# charger.net
KiCad netlist of a schematic drawn in EAGLE
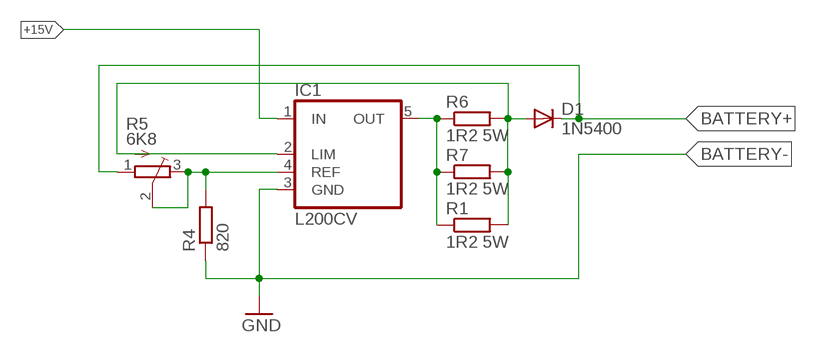
[diagram p0: schematic, sheet 1]

(export (version "E")
  (design (tool "Eeschema 10.0.6"))
  (components
    (comp (ref "D1")
      (value "1N5400")
      (footprint "eagle-import:DO201-15")
      (libsource (lib "eagle-import") (part "1N5400"))
    )
    (comp (ref "IC1")
      (value "L200CV")
      (footprint "eagle-import:L200S")
      (libsource (lib "eagle-import") (part "L200"))
    )
    (comp (ref "R1")
      (value "1R2 5W")
      (footprint "eagle-import:0204_7")
      (libsource (lib "eagle-import") (part "R-EU_0204/7"))
    )
    (comp (ref "R4")
      (value "820")
      (footprint "eagle-import:0204_7")
      (libsource (lib "eagle-import") (part "R-EU_0204/7"))
    )
    (comp (ref "R5")
      (value "6K8")
      (footprint "eagle-import:3223G")
      (libsource (lib "eagle-import") (part "TRIM_EU-3223G"))
    )
    (comp (ref "R6")
      (value "1R2 5W")
      (footprint "eagle-import:0204_7")
      (libsource (lib "eagle-import") (part "R-EU_0204/7"))
    )
    (comp (ref "R7")
      (value "1R2 5W")
      (footprint "eagle-import:0204_7")
      (libsource (lib "eagle-import") (part "R-EU_0204/7"))
    )
  )
  (nets
    (net (code "1") (name "+15V") (class "Default")
      (node (ref "IC1") (pin "1") (pinfunction "IN_1") (pintype "input"))
    )
    (net (code "2") (name "BATTERY+") (class "Default")
      (node (ref "D1") (pin "C") (pinfunction "C_C") (pintype "passive"))
      (node (ref "R5") (pin "1") (pinfunction "A_1") (pintype "passive"))
    )
    (net (code "3") (name "BATTERY-") (class "Default")
      (node (ref "IC1") (pin "3") (pinfunction "GND_3") (pintype "passive"))
      (node (ref "R4") (pin "1") (pinfunction "1_1") (pintype "passive"))
    )
    (net (code "4") (name "Net-(IC1-LIM)") (class "Default")
      (node (ref "D1") (pin "A") (pinfunction "A_A") (pintype "passive"))
      (node (ref "IC1") (pin "2") (pinfunction "LIM_2") (pintype "input"))
      (node (ref "R1") (pin "2") (pinfunction "2_2") (pintype "passive"))
      (node (ref "R6") (pin "2") (pinfunction "2_2") (pintype "passive"))
      (node (ref "R7") (pin "2") (pinfunction "2_2") (pintype "passive"))
    )
    (net (code "5") (name "Net-(IC1-OUT)") (class "Default")
      (node (ref "IC1") (pin "5") (pinfunction "OUT_5") (pintype "passive"))
      (node (ref "R1") (pin "1") (pinfunction "1_1") (pintype "passive"))
      (node (ref "R6") (pin "1") (pinfunction "1_1") (pintype "passive"))
      (node (ref "R7") (pin "1") (pinfunction "1_1") (pintype "passive"))
    )
    (net (code "6") (name "Net-(IC1-REF)") (class "Default")
      (node (ref "IC1") (pin "4") (pinfunction "REF_4") (pintype "input"))
      (node (ref "R4") (pin "2") (pinfunction "2_2") (pintype "passive"))
      (node (ref "R5") (pin "2") (pinfunction "S_2") (pintype "passive"))
      (node (ref "R5") (pin "3") (pinfunction "E_3") (pintype "passive"))
    )
  )
)
